# NightLightWiring.net
KiCad netlist of a schematic drawn in EAGLE
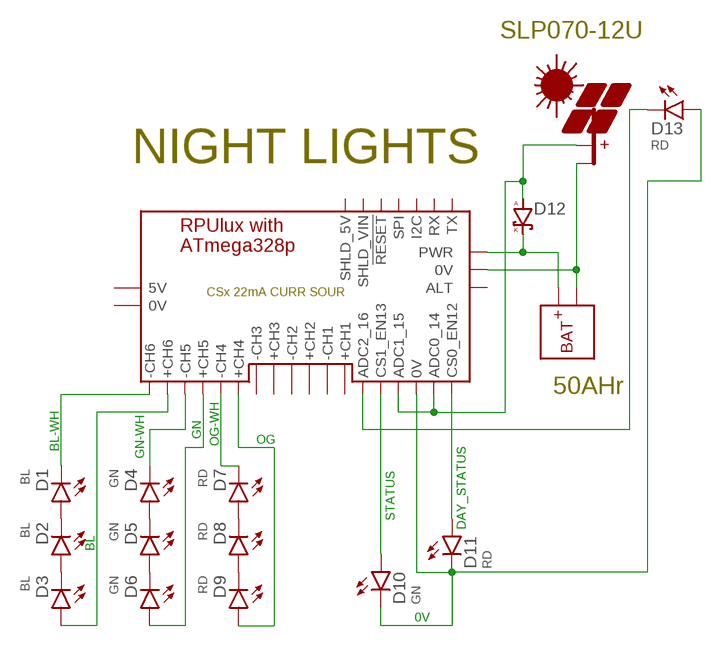
[diagram p0: schematic, sheet 1]

(export (version "E")
  (design (tool "Eeschema 10.0.6"))
  (components
    (comp (ref "D1")
      (value "BL")
      (footprint "eagle-import:LED5MM")
      (libsource (lib "eagle-import") (part "LED5MM"))
    )
    (comp (ref "D2")
      (value "BL")
      (footprint "eagle-import:LED5MM")
      (libsource (lib "eagle-import") (part "LED5MM"))
    )
    (comp (ref "D3")
      (value "BL")
      (footprint "eagle-import:LED5MM")
      (libsource (lib "eagle-import") (part "LED5MM"))
    )
    (comp (ref "D4")
      (value "GN")
      (footprint "eagle-import:LED5MM")
      (libsource (lib "eagle-import") (part "LED5MM"))
    )
    (comp (ref "D5")
      (value "GN")
      (footprint "eagle-import:LED5MM")
      (libsource (lib "eagle-import") (part "LED5MM"))
    )
    (comp (ref "D6")
      (value "GN")
      (footprint "eagle-import:LED5MM")
      (libsource (lib "eagle-import") (part "LED5MM"))
    )
    (comp (ref "D7")
      (value "RD")
      (footprint "eagle-import:LED5MM")
      (libsource (lib "eagle-import") (part "LED5MM"))
    )
    (comp (ref "D8")
      (value "RD")
      (footprint "eagle-import:LED5MM")
      (libsource (lib "eagle-import") (part "LED5MM"))
    )
    (comp (ref "D9")
      (value "RD")
      (footprint "eagle-import:LED5MM")
      (libsource (lib "eagle-import") (part "LED5MM"))
    )
    (comp (ref "D10")
      (value "GN")
      (footprint "eagle-import:LED5MM")
      (libsource (lib "eagle-import") (part "LED5MM"))
    )
    (comp (ref "D11")
      (value "RD")
      (footprint "eagle-import:LED5MM")
      (libsource (lib "eagle-import") (part "LED5MM"))
    )
    (comp (ref "D12")
      (value "DSMB")
      (footprint "eagle-import:SMB")
      (libsource (lib "eagle-import") (part "DSMB"))
    )
    (comp (ref "D13")
      (value "RD")
      (footprint "eagle-import:LED5MM")
      (libsource (lib "eagle-import") (part "LED5MM"))
    )
    (comp (ref "PV2")
      (value "PV")
      (footprint "eagle-import:NA-30")
      (libsource (lib "eagle-import") (part "PV"))
    )
    (comp (ref "U$1")
      (value "RPULUX")
      (footprint "eagle-import:WITH_RPU_NAMES")
      (libsource (lib "eagle-import") (part "RPULUX"))
    )
    (comp (ref "U$9")
      (value "BAT")
      (footprint "eagle-import:NA-30")
      (libsource (lib "eagle-import") (part "BAT"))
    )
  )
  (nets
    (net (code "1") (name "/0V") (class "Default")
      (node (ref "D10") (pin "K") (pinfunction "K_K") (pintype "passive"))
      (node (ref "D11") (pin "K") (pinfunction "K_K") (pintype "passive"))
      (node (ref "D13") (pin "A") (pinfunction "A_A") (pintype "passive"))
      (node (ref "U$1") (pin "0V@DIO2") (pinfunction "0V_0V@DIO2") (pintype "bidirectional"))
    )
    (net (code "2") (name "/BL") (class "Default")
      (node (ref "D3") (pin "A") (pinfunction "A_A") (pintype "passive"))
      (node (ref "U$1") (pin "+CH6") (pinfunction "+CH6_+CH6") (pintype "bidirectional"))
    )
    (net (code "3") (name "/BL-WH") (class "Default")
      (node (ref "D1") (pin "K") (pinfunction "K_K") (pintype "passive"))
      (node (ref "U$1") (pin "-CH6") (pinfunction "-CH6_-CH6") (pintype "bidirectional"))
    )
    (net (code "4") (name "/DAY_STATUS") (class "Default")
      (node (ref "D11") (pin "A") (pinfunction "A_A") (pintype "passive"))
      (node (ref "U$1") (pin "22MA@ADC0") (pinfunction "CS0_EN12_22MA@ADC0") (pintype "bidirectional"))
    )
    (net (code "5") (name "/GN") (class "Default")
      (node (ref "D6") (pin "A") (pinfunction "A_A") (pintype "passive"))
      (node (ref "U$1") (pin "+CH5") (pinfunction "+CH5_+CH5") (pintype "bidirectional"))
    )
    (net (code "6") (name "/GN-WH") (class "Default")
      (node (ref "D4") (pin "K") (pinfunction "K_K") (pintype "passive"))
      (node (ref "U$1") (pin "-CH5") (pinfunction "-CH5_-CH5") (pintype "bidirectional"))
    )
    (net (code "7") (name "/OG") (class "Default")
      (node (ref "D9") (pin "A") (pinfunction "A_A") (pintype "passive"))
      (node (ref "U$1") (pin "+CH4") (pinfunction "+CH4_+CH4") (pintype "bidirectional"))
    )
    (net (code "8") (name "/OG-WH") (class "Default")
      (node (ref "D7") (pin "K") (pinfunction "K_K") (pintype "passive"))
      (node (ref "U$1") (pin "-CH4") (pinfunction "-CH4_-CH4") (pintype "bidirectional"))
    )
    (net (code "9") (name "/STATUS") (class "Default")
      (node (ref "D10") (pin "A") (pinfunction "A_A") (pintype "passive"))
      (node (ref "U$1") (pin "22MA@ADC1") (pinfunction "CS1_EN13_22MA@ADC1") (pintype "bidirectional"))
    )
    (net (code "10") (name "Net-(D1-PadA)") (class "Default")
      (node (ref "D1") (pin "A") (pinfunction "A_A") (pintype "passive"))
      (node (ref "D2") (pin "K") (pinfunction "K_K") (pintype "passive"))
    )
    (net (code "11") (name "Net-(D2-PadA)") (class "Default")
      (node (ref "D2") (pin "A") (pinfunction "A_A") (pintype "passive"))
      (node (ref "D3") (pin "K") (pinfunction "K_K") (pintype "passive"))
    )
    (net (code "12") (name "Net-(D4-PadA)") (class "Default")
      (node (ref "D4") (pin "A") (pinfunction "A_A") (pintype "passive"))
      (node (ref "D5") (pin "K") (pinfunction "K_K") (pintype "passive"))
    )
    (net (code "13") (name "Net-(D5-PadA)") (class "Default")
      (node (ref "D5") (pin "A") (pinfunction "A_A") (pintype "passive"))
      (node (ref "D6") (pin "K") (pinfunction "K_K") (pintype "passive"))
    )
    (net (code "14") (name "Net-(D7-PadA)") (class "Default")
      (node (ref "D7") (pin "A") (pinfunction "A_A") (pintype "passive"))
      (node (ref "D8") (pin "K") (pinfunction "K_K") (pintype "passive"))
    )
    (net (code "15") (name "Net-(D8-PadA)") (class "Default")
      (node (ref "D8") (pin "A") (pinfunction "A_A") (pintype "passive"))
      (node (ref "D9") (pin "K") (pinfunction "K_K") (pintype "passive"))
    )
    (net (code "16") (name "Net-(PV2-+PV)") (class "Default")
      (node (ref "D12") (pin "A") (pinfunction "A_A") (pintype "passive"))
      (node (ref "PV2") (pin "1") (pinfunction "+PV_1") (pintype "bidirectional"))
      (node (ref "U$1") (pin "ADC0") (pinfunction "ADC0_14_ADC0") (pintype "bidirectional"))
      (node (ref "U$1") (pin "ADC1") (pinfunction "ADC1_15_ADC1") (pintype "bidirectional"))
    )
    (net (code "17") (name "Net-(PV2--PV)") (class "Default")
      (node (ref "PV2") (pin "2") (pinfunction "-PV_2") (pintype "bidirectional"))
      (node (ref "U$1") (pin "0V@PWR") (pinfunction "0V_0V@PWR") (pintype "bidirectional"))
      (node (ref "U$9") (pin "2") (pinfunction "-BAT_2") (pintype "bidirectional"))
    )
    (net (code "18") (name "Net-(U$1-ADC2_16)") (class "Default")
      (node (ref "D13") (pin "K") (pinfunction "K_K") (pintype "passive"))
      (node (ref "U$1") (pin "ADC2") (pinfunction "ADC2_16_ADC2") (pintype "bidirectional"))
    )
    (net (code "19") (name "Net-(U$9-+BAT)") (class "Default")
      (node (ref "D12") (pin "K") (pinfunction "K_K") (pintype "passive"))
      (node (ref "U$1") (pin "PWR") (pinfunction "PWR_PWR") (pintype "bidirectional"))
      (node (ref "U$9") (pin "1") (pinfunction "+BAT_1") (pintype "bidirectional"))
    )
    (net (code "20") (name "unconnected-(U$1-ALT-PadAUX)") (class "Default")
      (node (ref "U$1") (pin "AUX") (pinfunction "ALT_AUX") (pintype "bidirectional"))
    )
    (net (code "21") (name "unconnected-(U$1-Pad+CH1)") (class "Default")
      (node (ref "U$1") (pin "+CH1") (pinfunction "+CH1_+CH1") (pintype "bidirectional"))
    )
    (net (code "22") (name "unconnected-(U$1-Pad+CH2)") (class "Default")
      (node (ref "U$1") (pin "+CH2") (pinfunction "+CH2_+CH2") (pintype "bidirectional"))
    )
    (net (code "23") (name "unconnected-(U$1-Pad+CH3)") (class "Default")
      (node (ref "U$1") (pin "+CH3") (pinfunction "+CH3_+CH3") (pintype "bidirectional"))
    )
    (net (code "24") (name "unconnected-(U$1-Pad-CH1)") (class "Default")
      (node (ref "U$1") (pin "-CH1") (pinfunction "-CH1_-CH1") (pintype "bidirectional"))
    )
    (net (code "25") (name "unconnected-(U$1-Pad-CH2)") (class "Default")
      (node (ref "U$1") (pin "-CH2") (pinfunction "-CH2_-CH2") (pintype "bidirectional"))
    )
    (net (code "26") (name "unconnected-(U$1-Pad-CH3)") (class "Default")
      (node (ref "U$1") (pin "-CH3") (pinfunction "-CH3_-CH3") (pintype "bidirectional"))
    )
    (net (code "27") (name "unconnected-(U$1-Pad0V)") (class "Default")
      (node (ref "U$1") (pin "0V") (pinfunction "0V_0V") (pintype "bidirectional"))
    )
    (net (code "28") (name "unconnected-(U$1-Pad5V)") (class "Default")
      (node (ref "U$1") (pin "5V") (pinfunction "5V_5V") (pintype "bidirectional"))
    )
    (net (code "29") (name "unconnected-(U$1-PadI2C)") (class "Default")
      (node (ref "U$1") (pin "I2C") (pinfunction "I2C_I2C") (pintype "bidirectional"))
    )
    (net (code "30") (name "unconnected-(U$1-PadRX)") (class "Default")
      (node (ref "U$1") (pin "RX") (pinfunction "RX_RX") (pintype "bidirectional"))
    )
    (net (code "31") (name "unconnected-(U$1-PadSHLD_5V)") (class "Default")
      (node (ref "U$1") (pin "SHLD_5V") (pinfunction "SHLD_5V_SHLD_5V") (pintype "bidirectional"))
    )
    (net (code "32") (name "unconnected-(U$1-PadSPI)") (class "Default")
      (node (ref "U$1") (pin "SPI") (pinfunction "SPI_SPI") (pintype "bidirectional"))
    )
    (net (code "33") (name "unconnected-(U$1-PadTX)") (class "Default")
      (node (ref "U$1") (pin "TX") (pinfunction "TX_TX") (pintype "bidirectional"))
    )
    (net (code "34") (name "unconnected-(U$1-SHLD_VIN-PadSHLD_VOUT)") (class "Default")
      (node (ref "U$1") (pin "SHLD_VOUT") (pinfunction "SHLD_VIN_SHLD_VOUT") (pintype "bidirectional"))
    )
    (net (code "35") (name "unconnected-(U$1-~{RESET}-Pad!RESET)") (class "Default")
      (node (ref "U$1") (pin "!RESET") (pinfunction "~{RESET}_!RESET") (pintype "bidirectional"))
    )
  )
)
